# GPRS_Tracker_Sensors.net
KiCad netlist of a schematic drawn in EAGLE
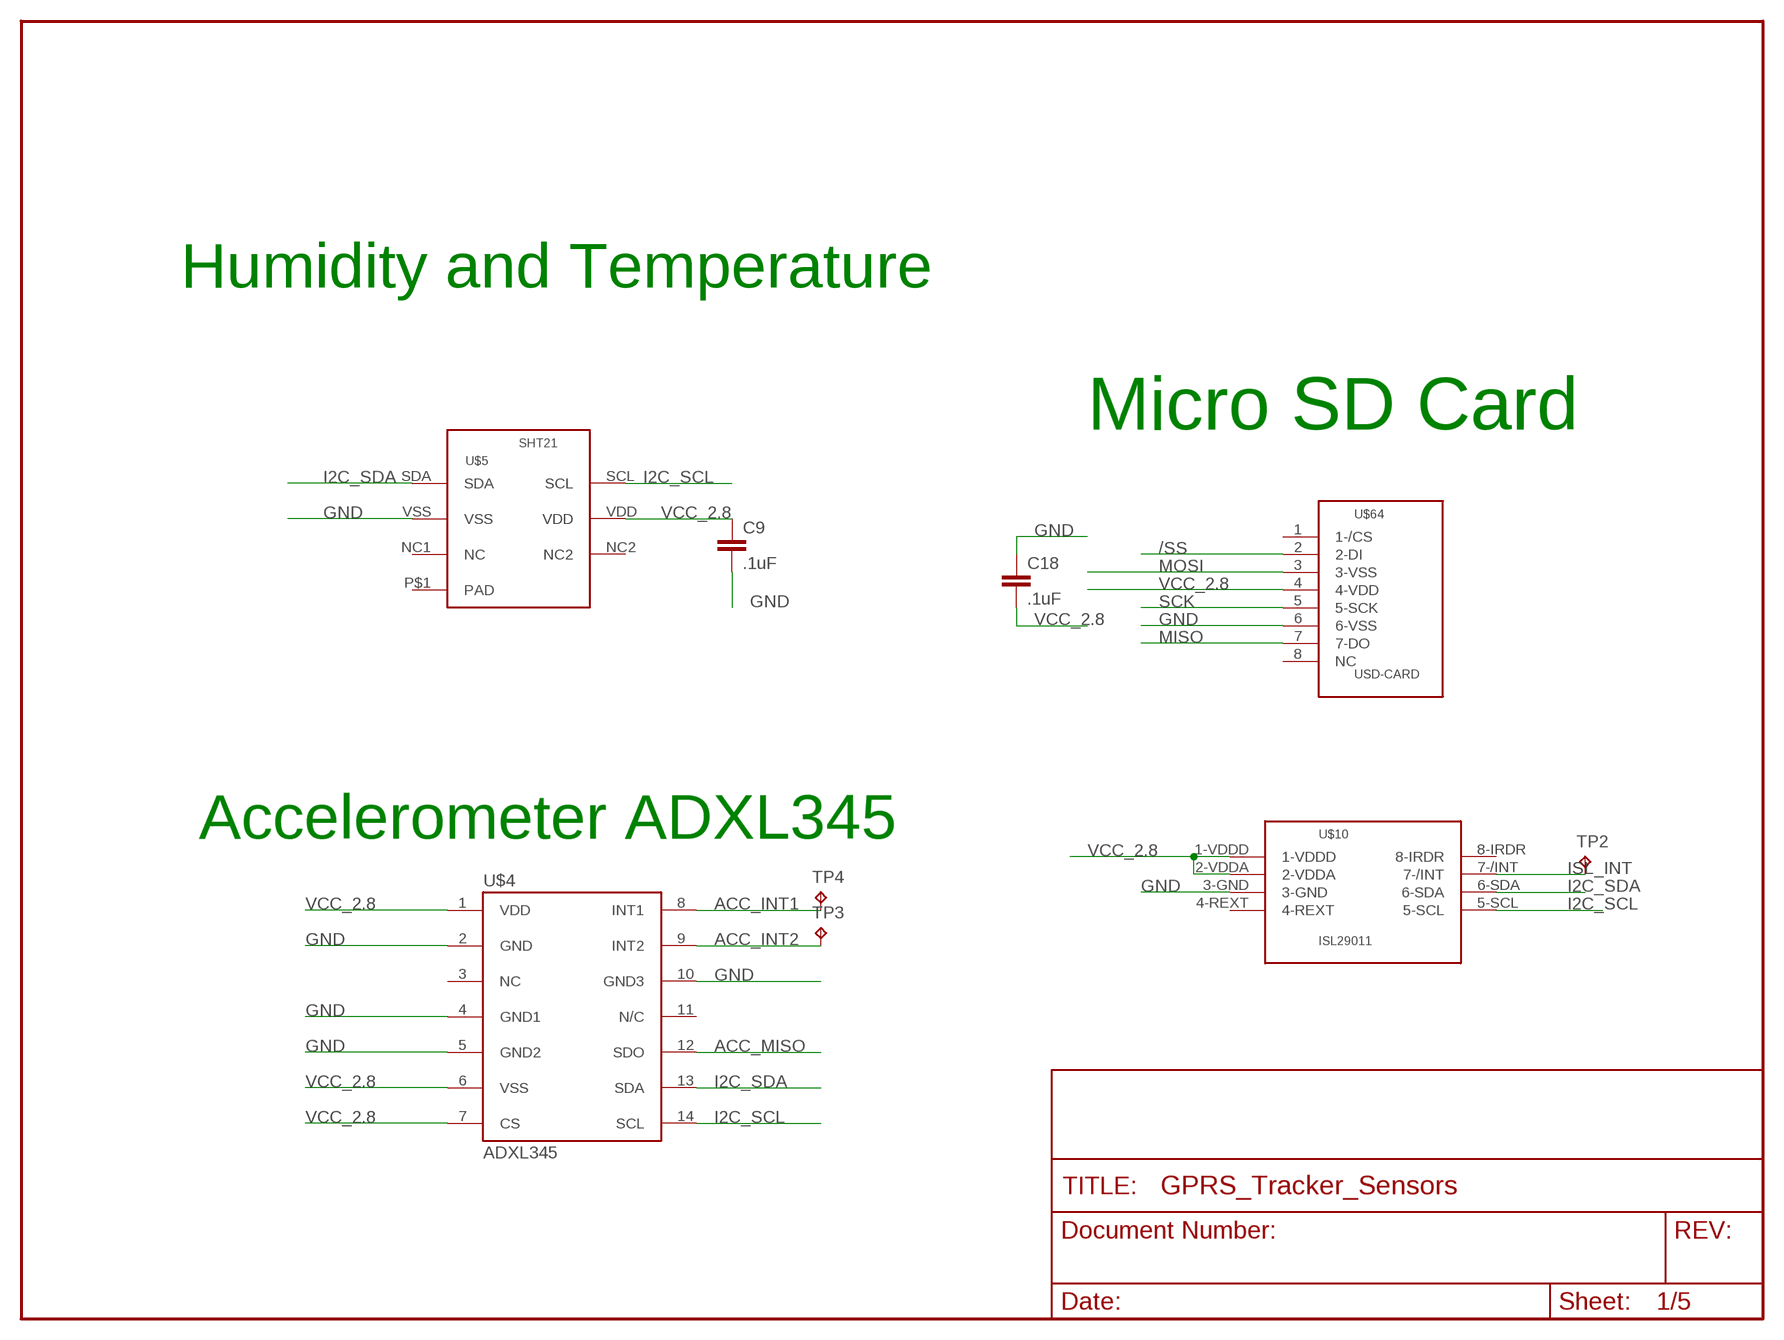
[diagram p0: schematic, sheet 1]
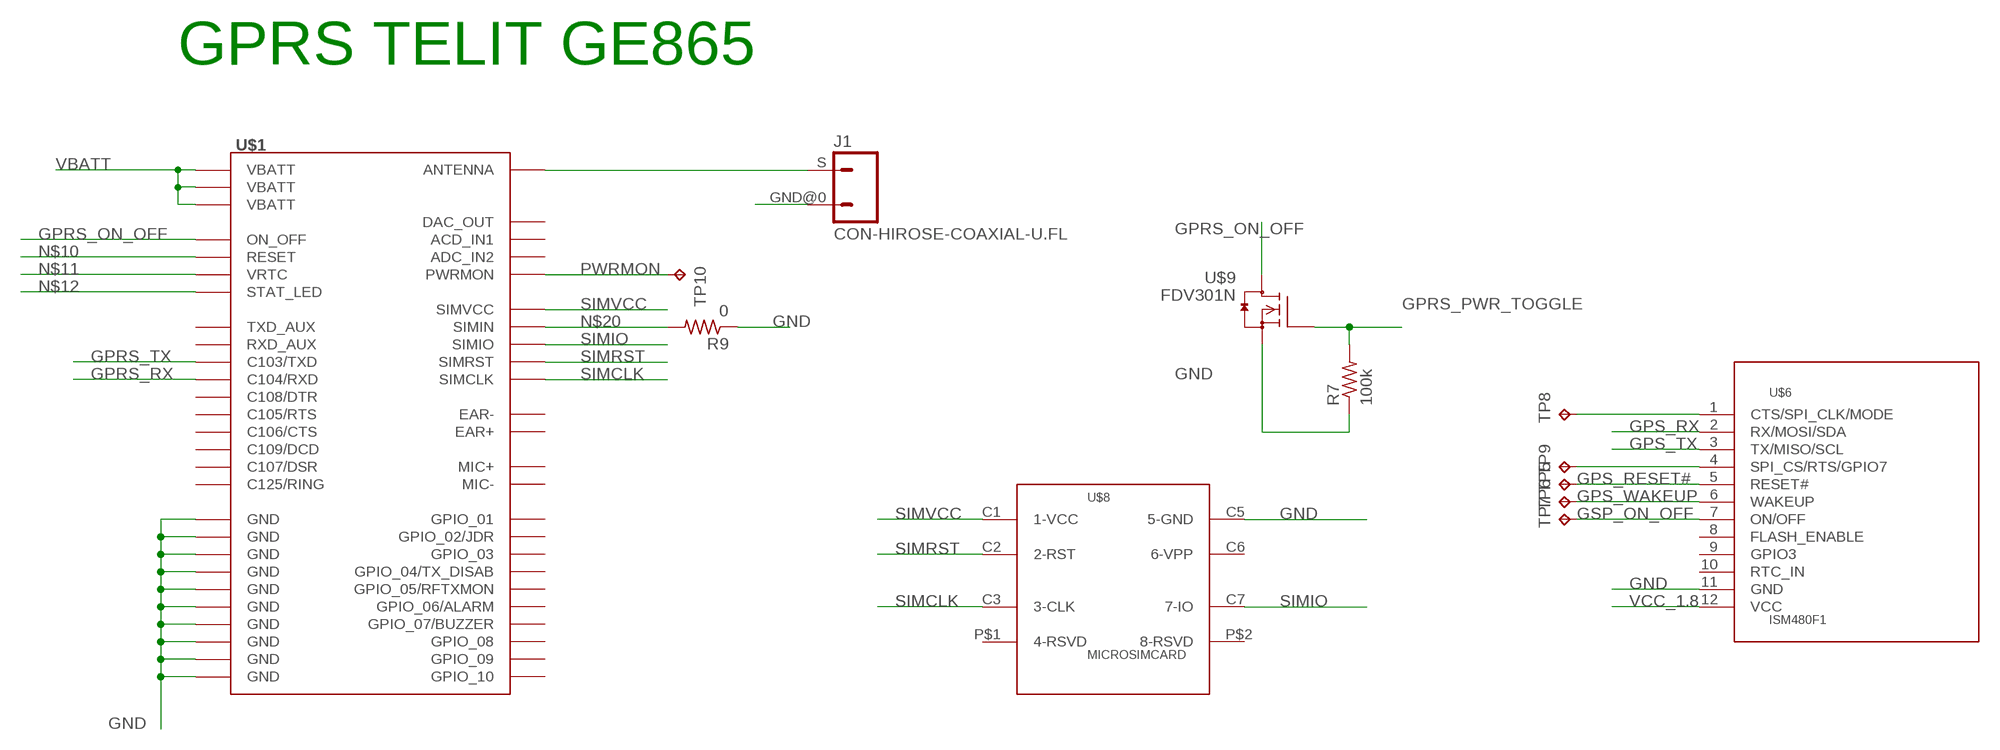
[diagram p1: schematic, sheet 2]
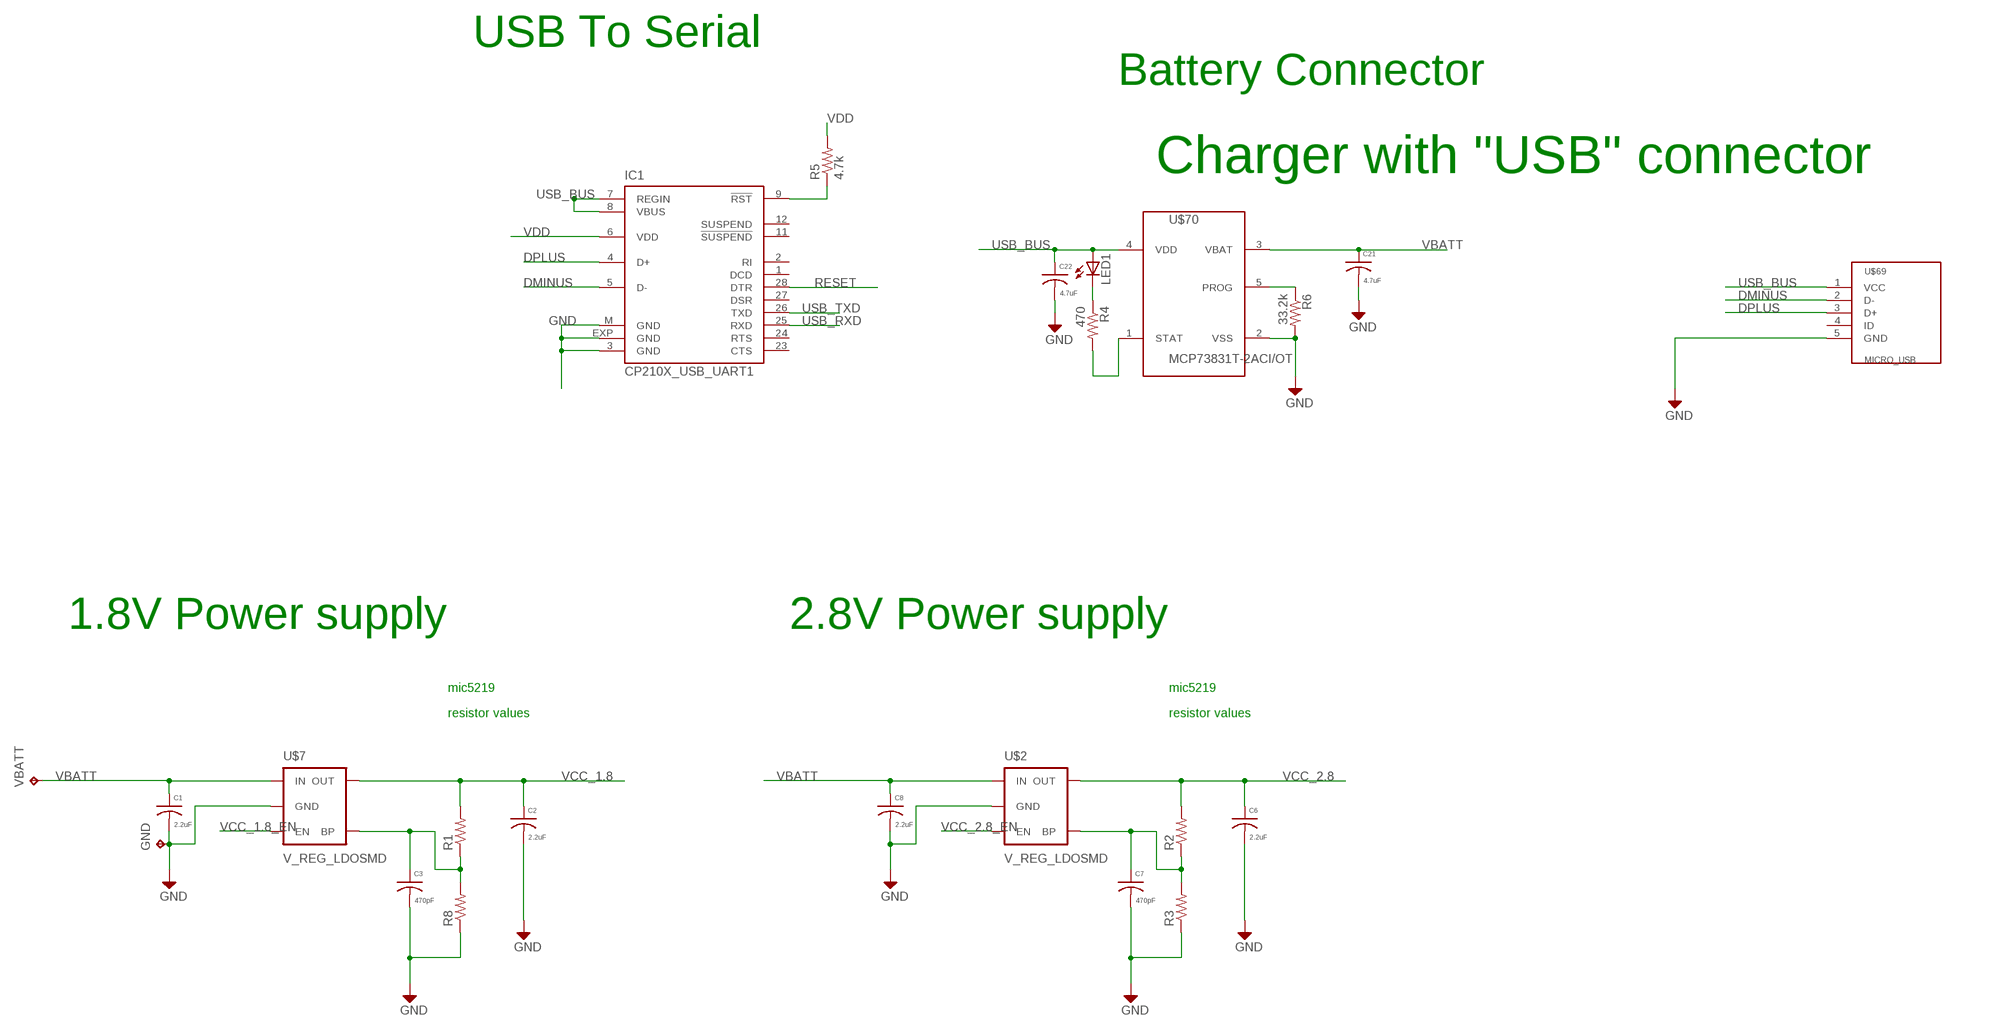
[diagram p2: schematic, sheet 5]

(export (version "E")
  (design (tool "Eeschema 10.0.6"))
  (components
    (comp (ref "C1")
      (value "2.2uF")
      (footprint "eagle-import:C0603")
      (libsource (lib "eagle-import") (part "C0603"))
    )
    (comp (ref "C2")
      (value "2.2uF")
      (footprint "eagle-import:C0603")
      (libsource (lib "eagle-import") (part "C0603"))
    )
    (comp (ref "C3")
      (value "470pF")
      (footprint "eagle-import:C0402")
      (libsource (lib "eagle-import") (part "C0402"))
    )
    (comp (ref "C6")
      (value "2.2uF")
      (footprint "eagle-import:C0603")
      (libsource (lib "eagle-import") (part "C0603"))
    )
    (comp (ref "C7")
      (value "470pF")
      (footprint "eagle-import:C0402")
      (libsource (lib "eagle-import") (part "C0402"))
    )
    (comp (ref "C8")
      (value "2.2uF")
      (footprint "eagle-import:C0603")
      (libsource (lib "eagle-import") (part "C0603"))
    )
    (comp (ref "C21")
      (value "4.7uF")
      (footprint "eagle-import:C0603")
      (libsource (lib "eagle-import") (part "C0603"))
    )
    (comp (ref "C22")
      (value "4.7uF")
      (footprint "eagle-import:C0603")
      (libsource (lib "eagle-import") (part "C0603"))
    )
    (comp (ref "GND")
      (value "TPTP15R")
      (footprint "eagle-import:TP15R")
      (libsource (lib "eagle-import") (part "TPTP15R"))
    )
    (comp (ref "IC1")
      (value "CP210X_USB_UART1")
      (footprint "eagle-import:MLP28")
      (libsource (lib "eagle-import") (part "CP210X_USB_UART1"))
    )
    (comp (ref "LED1")
      (value "LEDCHIP-LED0603")
      (footprint "eagle-import:CHIP-LED0603")
      (libsource (lib "eagle-import") (part "LEDCHIP-LED0603"))
    )
    (comp (ref "R1")
      (value "R-US_R0402")
      (footprint "eagle-import:R0402")
      (libsource (lib "eagle-import") (part "R-US_R0402"))
    )
    (comp (ref "R2")
      (value "R-US_R0402")
      (footprint "eagle-import:R0402")
      (libsource (lib "eagle-import") (part "R-US_R0402"))
    )
    (comp (ref "R3")
      (value "R-US_R0402")
      (footprint "eagle-import:R0402")
      (libsource (lib "eagle-import") (part "R-US_R0402"))
    )
    (comp (ref "R4")
      (value "470")
      (footprint "eagle-import:R0402")
      (libsource (lib "eagle-import") (part "R-US_R0402"))
    )
    (comp (ref "R5")
      (value "4.7k")
      (footprint "eagle-import:R0402")
      (libsource (lib "eagle-import") (part "R-US_R0402"))
    )
    (comp (ref "R6")
      (value "33.2k")
      (footprint "eagle-import:R0402")
      (libsource (lib "eagle-import") (part "R-US_R0402"))
    )
    (comp (ref "R8")
      (value "R-US_R0402")
      (footprint "eagle-import:R0402")
      (libsource (lib "eagle-import") (part "R-US_R0402"))
    )
    (comp (ref "U$2")
      (value "V_REG_LDOSMD")
      (footprint "eagle-import:SOT23-5")
      (libsource (lib "eagle-import") (part "V_REG_LDOSMD"))
    )
    (comp (ref "U$7")
      (value "V_REG_LDOSMD")
      (footprint "eagle-import:SOT23-5")
      (libsource (lib "eagle-import") (part "V_REG_LDOSMD"))
    )
    (comp (ref "U$69")
      (value "MICRO_USB")
      (footprint "eagle-import:MICRO_USB")
      (libsource (lib "eagle-import") (part "MICRO_USB"))
    )
    (comp (ref "U$70")
      (value "MCP73831T-2ACI/OT")
      (footprint "eagle-import:SOT23-5L")
      (libsource (lib "eagle-import") (part "MCP73831T-2ACI/OT"))
    )
    (comp (ref "VBATT")
      (value "TPTP15R")
      (footprint "eagle-import:TP15R")
      (libsource (lib "eagle-import") (part "TPTP15R"))
    )
    (comp (ref "C9")
      (value ".1uF")
      (footprint "eagle-import:C0402")
      (libsource (lib "eagle-import") (part "C-EUC0402"))
    )
    (comp (ref "C18")
      (value ".1uF")
      (footprint "eagle-import:C0402")
      (libsource (lib "eagle-import") (part "C-EUC0402"))
    )
    (comp (ref "TP2")
      (value "TPTP08R")
      (footprint "eagle-import:TP08R")
      (libsource (lib "eagle-import") (part "TPTP08R"))
    )
    (comp (ref "TP3")
      (value "TPTP06R")
      (footprint "eagle-import:TP06R")
      (libsource (lib "eagle-import") (part "TPTP06R"))
    )
    (comp (ref "TP4")
      (value "TPTP06R")
      (footprint "eagle-import:TP06R")
      (libsource (lib "eagle-import") (part "TPTP06R"))
    )
    (comp (ref "U$4")
      (value "ADXL345")
      (footprint "eagle-import:LGA14")
      (libsource (lib "eagle-import") (part "ADXL345"))
    )
    (comp (ref "U$5")
      (value "SHT21")
      (footprint "eagle-import:SHT21")
      (libsource (lib "eagle-import") (part "SHT21"))
    )
    (comp (ref "U$10")
      (value "ISL29011")
      (footprint "eagle-import:ISL29011")
      (libsource (lib "eagle-import") (part "ISL29011"))
    )
    (comp (ref "U$64")
      (value "USD-CARD")
      (footprint "eagle-import:502774-0891")
      (libsource (lib "eagle-import") (part "USD-CARD"))
    )
    (comp (ref "J1")
      (value "CON-HIROSE-COAXIAL-U.FL")
      (footprint "eagle-import:CON-U.FL")
      (libsource (lib "eagle-import") (part "CON-HIROSE-COAXIAL-U.FL"))
    )
    (comp (ref "R7")
      (value "100k")
      (footprint "eagle-import:R0402")
      (libsource (lib "eagle-import") (part "resistor_R-US_R0402"))
    )
    (comp (ref "R9")
      (value "0")
      (footprint "eagle-import:R0402")
      (libsource (lib "eagle-import") (part "resistor_R-US_R0402"))
    )
    (comp (ref "TP5")
      (value "TPTP06R")
      (footprint "eagle-import:TP06R")
      (libsource (lib "eagle-import") (part "TPTP06R"))
    )
    (comp (ref "TP6")
      (value "TPTP06R")
      (footprint "eagle-import:TP06R")
      (libsource (lib "eagle-import") (part "TPTP06R"))
    )
    (comp (ref "TP7")
      (value "TPTP06R")
      (footprint "eagle-import:TP06R")
      (libsource (lib "eagle-import") (part "TPTP06R"))
    )
    (comp (ref "TP8")
      (value "TPTP06R")
      (footprint "eagle-import:TP06R")
      (libsource (lib "eagle-import") (part "TPTP06R"))
    )
    (comp (ref "TP9")
      (value "TPTP06R")
      (footprint "eagle-import:TP06R")
      (libsource (lib "eagle-import") (part "TPTP06R"))
    )
    (comp (ref "TP10")
      (value "TPTP06R")
      (footprint "eagle-import:TP06R")
      (libsource (lib "eagle-import") (part "TPTP06R"))
    )
    (comp (ref "U$1")
      (value "GE865")
      (footprint "eagle-import:GE865")
      (libsource (lib "eagle-import") (part "GE865"))
    )
    (comp (ref "U$6")
      (value "ISM480F1")
      (footprint "eagle-import:20488-012E-01")
      (libsource (lib "eagle-import") (part "ISM480F1"))
    )
    (comp (ref "U$8")
      (value "MICROSIMCARD")
      (footprint "eagle-import:FMS006-5000-0")
      (libsource (lib "eagle-import") (part "MICROSIMCARD"))
    )
    (comp (ref "U$9")
      (value "FDV301N")
      (footprint "eagle-import:SOT23")
      (libsource (lib "eagle-import") (part "FDV301N"))
    )
  )
  (nets
    (net (code "1") (name "ACC_INT1") (class "Default")
      (node (ref "TP4") (pin "TP") (pinfunction "TP_TP") (pintype "input"))
      (node (ref "U$4") (pin "8") (pinfunction "INT1_8") (pintype "bidirectional"))
    )
    (net (code "2") (name "ACC_INT2") (class "Default")
      (node (ref "TP3") (pin "TP") (pinfunction "TP_TP") (pintype "input"))
      (node (ref "U$4") (pin "9") (pinfunction "INT2_9") (pintype "bidirectional"))
    )
    (net (code "3") (name "ACC_MISO") (class "Default")
      (node (ref "U$4") (pin "12") (pinfunction "SDO_12") (pintype "bidirectional"))
    )
    (net (code "4") (name "DMINUS") (class "Default")
      (node (ref "IC1") (pin "5") (pinfunction "D-_5") (pintype "bidirectional"))
      (node (ref "U$69") (pin "2") (pinfunction "D-_2") (pintype "bidirectional"))
    )
    (net (code "5") (name "DPLUS") (class "Default")
      (node (ref "IC1") (pin "4") (pinfunction "D+_4") (pintype "bidirectional"))
      (node (ref "U$69") (pin "3") (pinfunction "D+_3") (pintype "bidirectional"))
    )
    (net (code "6") (name "GND") (class "Default")
      (node (ref "C1") (pin "2") (pinfunction "2_2") (pintype "passive"))
      (node (ref "C18") (pin "1") (pinfunction "1_1") (pintype "passive"))
      (node (ref "C2") (pin "2") (pinfunction "2_2") (pintype "passive"))
      (node (ref "C21") (pin "2") (pinfunction "2_2") (pintype "passive"))
      (node (ref "C22") (pin "2") (pinfunction "2_2") (pintype "passive"))
      (node (ref "C3") (pin "2") (pinfunction "2_2") (pintype "passive"))
      (node (ref "C6") (pin "2") (pinfunction "2_2") (pintype "passive"))
      (node (ref "C7") (pin "2") (pinfunction "2_2") (pintype "passive"))
      (node (ref "C8") (pin "2") (pinfunction "2_2") (pintype "passive"))
      (node (ref "C9") (pin "2") (pinfunction "2_2") (pintype "passive"))
      (node (ref "GND") (pin "TP") (pinfunction "TP_TP") (pintype "input"))
      (node (ref "IC1") (pin "3") (pinfunction "GND_3") (pintype "power_in"))
      (node (ref "IC1") (pin "EXP") (pinfunction "GND_EXP") (pintype "power_in"))
      (node (ref "IC1") (pin "M") (pinfunction "GND_M") (pintype "power_in"))
      (node (ref "R3") (pin "1") (pinfunction "1_1") (pintype "passive"))
      (node (ref "R6") (pin "2") (pinfunction "2_2") (pintype "passive"))
      (node (ref "R7") (pin "1") (pinfunction "1_1") (pintype "passive"))
      (node (ref "R8") (pin "1") (pinfunction "1_1") (pintype "passive"))
      (node (ref "R9") (pin "1") (pinfunction "1_1") (pintype "passive"))
      (node (ref "U$1") (pin "C2") (pinfunction "GND_C2") (pintype "bidirectional"))
      (node (ref "U$1") (pin "C7") (pinfunction "GND_C7") (pintype "bidirectional"))
      (node (ref "U$1") (pin "E5") (pinfunction "GND_E5") (pintype "bidirectional"))
      (node (ref "U$1") (pin "E7") (pinfunction "GND_E7") (pintype "bidirectional"))
      (node (ref "U$1") (pin "G1") (pinfunction "GND_G1") (pintype "bidirectional"))
      (node (ref "U$1") (pin "G3") (pinfunction "GND_G3") (pintype "bidirectional"))
      (node (ref "U$1") (pin "G4") (pinfunction "GND_G4") (pintype "bidirectional"))
      (node (ref "U$1") (pin "G5") (pinfunction "GND_G5") (pintype "bidirectional"))
      (node (ref "U$1") (pin "H3") (pinfunction "GND_H3") (pintype "bidirectional"))
      (node (ref "U$1") (pin "H6") (pinfunction "GND_H6") (pintype "bidirectional"))
      (node (ref "U$10") (pin "3-GND") (pinfunction "3-GND_3-GND") (pintype "bidirectional"))
      (node (ref "U$2") (pin "2") (pinfunction "GND_2") (pintype "input"))
      (node (ref "U$4") (pin "10") (pinfunction "GND3_10") (pintype "bidirectional"))
      (node (ref "U$4") (pin "2") (pinfunction "GND_2") (pintype "bidirectional"))
      (node (ref "U$4") (pin "4") (pinfunction "GND1_4") (pintype "bidirectional"))
      (node (ref "U$4") (pin "5") (pinfunction "GND2_5") (pintype "bidirectional"))
      (node (ref "U$5") (pin "VSS") (pinfunction "VSS_VSS") (pintype "bidirectional"))
      (node (ref "U$6") (pin "11") (pinfunction "GND_11") (pintype "bidirectional"))
      (node (ref "U$64") (pin "6") (pinfunction "6-VSS_6") (pintype "bidirectional"))
      (node (ref "U$69") (pin "5") (pinfunction "GND_5") (pintype "bidirectional"))
      (node (ref "U$7") (pin "2") (pinfunction "GND_2") (pintype "input"))
      (node (ref "U$70") (pin "2") (pinfunction "VSS_2") (pintype "bidirectional"))
      (node (ref "U$8") (pin "C5") (pinfunction "5-GND_C5") (pintype "bidirectional"))
      (node (ref "U$9") (pin "2") (pinfunction "S_2") (pintype "passive"))
    )
    (net (code "7") (name "GPRS_ON_OFF") (class "Default")
      (node (ref "U$1") (pin "B1") (pinfunction "ON_OFF_B1") (pintype "bidirectional"))
      (node (ref "U$9") (pin "3") (pinfunction "D_3") (pintype "passive"))
    )
    (net (code "8") (name "GPRS_PWR_TOGGLE") (class "Default")
      (node (ref "R7") (pin "2") (pinfunction "2_2") (pintype "passive"))
      (node (ref "U$9") (pin "1") (pinfunction "G_1") (pintype "passive"))
    )
    (net (code "9") (name "GPRS_RX") (class "Default")
      (node (ref "U$1") (pin "A4") (pinfunction "C104/RXD_A4") (pintype "bidirectional"))
    )
    (net (code "10") (name "GPRS_TX") (class "Default")
      (node (ref "U$1") (pin "A3") (pinfunction "C103/TXD_A3") (pintype "bidirectional"))
    )
    (net (code "11") (name "GPS_RESET#") (class "Default")
      (node (ref "TP5") (pin "TP") (pinfunction "TP_TP") (pintype "input"))
      (node (ref "U$6") (pin "5") (pinfunction "RESET#_5") (pintype "bidirectional"))
    )
    (net (code "12") (name "GPS_RX") (class "Default")
      (node (ref "U$6") (pin "2") (pinfunction "RX/MOSI/SDA_2") (pintype "bidirectional"))
    )
    (net (code "13") (name "GPS_TX") (class "Default")
      (node (ref "U$6") (pin "3") (pinfunction "TX/MISO/SCL_3") (pintype "bidirectional"))
    )
    (net (code "14") (name "GPS_WAKEUP") (class "Default")
      (node (ref "TP6") (pin "TP") (pinfunction "TP_TP") (pintype "input"))
      (node (ref "U$6") (pin "6") (pinfunction "WAKEUP_6") (pintype "bidirectional"))
    )
    (net (code "15") (name "GSP_ON_OFF") (class "Default")
      (node (ref "TP7") (pin "TP") (pinfunction "TP_TP") (pintype "input"))
      (node (ref "U$6") (pin "7") (pinfunction "ON/OFF_7") (pintype "bidirectional"))
    )
    (net (code "16") (name "I2C_SCL") (class "Default")
      (node (ref "U$10") (pin "5-SCL") (pinfunction "5-SCL_5-SCL") (pintype "bidirectional"))
      (node (ref "U$4") (pin "14") (pinfunction "SCL_14") (pintype "bidirectional"))
      (node (ref "U$5") (pin "SCL") (pinfunction "SCL_SCL") (pintype "bidirectional"))
    )
    (net (code "17") (name "I2C_SDA") (class "Default")
      (node (ref "U$10") (pin "6-SDA") (pinfunction "6-SDA_6-SDA") (pintype "bidirectional"))
      (node (ref "U$4") (pin "13") (pinfunction "SDA_13") (pintype "bidirectional"))
      (node (ref "U$5") (pin "SDA") (pinfunction "SDA_SDA") (pintype "bidirectional"))
    )
    (net (code "18") (name "ISL_INT") (class "Default")
      (node (ref "TP2") (pin "TP") (pinfunction "TP_TP") (pintype "input"))
      (node (ref "U$10") (pin "7-/INT") (pinfunction "7-/INT_7-/INT") (pintype "bidirectional"))
    )
    (net (code "19") (name "MISO") (class "Default")
      (node (ref "U$64") (pin "7") (pinfunction "7-DO_7") (pintype "bidirectional"))
    )
    (net (code "20") (name "MOSI") (class "Default")
      (node (ref "U$64") (pin "3") (pinfunction "3-VSS_3") (pintype "bidirectional"))
    )
    (net (code "21") (name "N$10") (class "Default")
      (node (ref "U$1") (pin "C1") (pinfunction "RESET_C1") (pintype "bidirectional"))
    )
    (net (code "22") (name "N$11") (class "Default")
      (node (ref "U$1") (pin "H2") (pinfunction "VRTC_H2") (pintype "bidirectional"))
    )
    (net (code "23") (name "N$12") (class "Default")
      (node (ref "U$1") (pin "G8") (pinfunction "STAT_LED_G8") (pintype "bidirectional"))
    )
    (net (code "24") (name "N$20") (class "Default")
      (node (ref "R9") (pin "2") (pinfunction "2_2") (pintype "passive"))
      (node (ref "U$1") (pin "B7") (pinfunction "SIMIN_B7") (pintype "bidirectional"))
    )
    (net (code "25") (name "Net-(IC1-~{RST})") (class "Default")
      (node (ref "IC1") (pin "9") (pinfunction "~{RST}_9") (pintype "bidirectional"))
      (node (ref "R5") (pin "1") (pinfunction "1_1") (pintype "passive"))
    )
    (net (code "26") (name "Net-(J1-1)") (class "Default")
      (node (ref "J1") (pin "S") (pinfunction "1_S") (pintype "passive"))
      (node (ref "U$1") (pin "H5") (pinfunction "ANTENNA_H5") (pintype "bidirectional"))
    )
    (net (code "27") (name "Net-(LED1-PadC)") (class "Default")
      (node (ref "LED1") (pin "C") (pinfunction "C_C") (pintype "passive"))
      (node (ref "R4") (pin "1") (pinfunction "1_1") (pintype "passive"))
    )
    (net (code "28") (name "Net-(U$2-BP)") (class "Default")
      (node (ref "C7") (pin "1") (pinfunction "1_1") (pintype "passive"))
      (node (ref "R2") (pin "1") (pinfunction "1_1") (pintype "passive"))
      (node (ref "R3") (pin "2") (pinfunction "2_2") (pintype "passive"))
      (node (ref "U$2") (pin "4") (pinfunction "BP_4") (pintype "input"))
    )
    (net (code "29") (name "Net-(U$6-CTS{slash}SPI_CLK{slash}MODE)") (class "Default")
      (node (ref "TP8") (pin "TP") (pinfunction "TP_TP") (pintype "input"))
      (node (ref "U$6") (pin "1") (pinfunction "CTS/SPI_CLK/MODE_1") (pintype "bidirectional"))
    )
    (net (code "30") (name "Net-(U$6-SPI_CS{slash}RTS{slash}GPIO7)") (class "Default")
      (node (ref "TP9") (pin "TP") (pinfunction "TP_TP") (pintype "input"))
      (node (ref "U$6") (pin "4") (pinfunction "SPI_CS/RTS/GPIO7_4") (pintype "bidirectional"))
    )
    (net (code "31") (name "Net-(U$7-BP)") (class "Default")
      (node (ref "C3") (pin "1") (pinfunction "1_1") (pintype "passive"))
      (node (ref "R1") (pin "1") (pinfunction "1_1") (pintype "passive"))
      (node (ref "R8") (pin "2") (pinfunction "2_2") (pintype "passive"))
      (node (ref "U$7") (pin "4") (pinfunction "BP_4") (pintype "input"))
    )
    (net (code "32") (name "Net-(U$70-PROG)") (class "Default")
      (node (ref "R6") (pin "1") (pinfunction "1_1") (pintype "passive"))
      (node (ref "U$70") (pin "5") (pinfunction "PROG_5") (pintype "bidirectional"))
    )
    (net (code "33") (name "Net-(U$70-STAT)") (class "Default")
      (node (ref "R4") (pin "2") (pinfunction "2_2") (pintype "passive"))
      (node (ref "U$70") (pin "1") (pinfunction "STAT_1") (pintype "bidirectional"))
    )
    (net (code "34") (name "PWRMON") (class "Default")
      (node (ref "TP10") (pin "TP") (pinfunction "TP_TP") (pintype "input"))
      (node (ref "U$1") (pin "E2") (pinfunction "PWRMON_E2") (pintype "bidirectional"))
    )
    (net (code "35") (name "RESET") (class "Default")
      (node (ref "IC1") (pin "28") (pinfunction "DTR_28") (pintype "output"))
    )
    (net (code "36") (name "SCK") (class "Default")
      (node (ref "U$64") (pin "5") (pinfunction "5-SCK_5") (pintype "bidirectional"))
    )
    (net (code "37") (name "SIMCLK") (class "Default")
      (node (ref "U$1") (pin "A5") (pinfunction "SIMCLK_A5") (pintype "bidirectional"))
      (node (ref "U$8") (pin "C3") (pinfunction "3-CLK_C3") (pintype "bidirectional"))
    )
    (net (code "38") (name "SIMIO") (class "Default")
      (node (ref "U$1") (pin "A6") (pinfunction "SIMIO_A6") (pintype "bidirectional"))
      (node (ref "U$8") (pin "C7") (pinfunction "7-IO_C7") (pintype "bidirectional"))
    )
    (net (code "39") (name "SIMRST") (class "Default")
      (node (ref "U$1") (pin "A8") (pinfunction "SIMRST_A8") (pintype "bidirectional"))
      (node (ref "U$8") (pin "C2") (pinfunction "2-RST_C2") (pintype "bidirectional"))
    )
    (net (code "40") (name "SIMVCC") (class "Default")
      (node (ref "U$1") (pin "A7") (pinfunction "SIMVCC_A7") (pintype "bidirectional"))
      (node (ref "U$8") (pin "C1") (pinfunction "1-VCC_C1") (pintype "bidirectional"))
    )
    (net (code "41") (name "USB_BUS") (class "Default")
      (node (ref "C22") (pin "1") (pinfunction "1_1") (pintype "passive"))
      (node (ref "IC1") (pin "7") (pinfunction "REGIN_7") (pintype "passive"))
      (node (ref "IC1") (pin "8") (pinfunction "VBUS_8") (pintype "input"))
      (node (ref "LED1") (pin "A") (pinfunction "A_A") (pintype "passive"))
      (node (ref "U$69") (pin "1") (pinfunction "VCC_1") (pintype "bidirectional"))
      (node (ref "U$70") (pin "4") (pinfunction "VDD_4") (pintype "bidirectional"))
    )
    (net (code "42") (name "USB_RXD") (class "Default")
      (node (ref "IC1") (pin "25") (pinfunction "RXD_25") (pintype "input"))
    )
    (net (code "43") (name "USB_TXD") (class "Default")
      (node (ref "IC1") (pin "26") (pinfunction "TXD_26") (pintype "output"))
    )
    (net (code "44") (name "VBATT") (class "Default")
      (node (ref "C1") (pin "1") (pinfunction "1_1") (pintype "passive"))
      (node (ref "C21") (pin "1") (pinfunction "1_1") (pintype "passive"))
      (node (ref "C8") (pin "1") (pinfunction "1_1") (pintype "passive"))
      (node (ref "U$1") (pin "F1") (pinfunction "VBATT_F1") (pintype "bidirectional"))
      (node (ref "U$1") (pin "F2") (pinfunction "VBATT_F2") (pintype "bidirectional"))
      (node (ref "U$1") (pin "F3") (pinfunction "VBATT_F3") (pintype "bidirectional"))
      (node (ref "U$2") (pin "1") (pinfunction "IN_1") (pintype "input"))
      (node (ref "U$7") (pin "1") (pinfunction "IN_1") (pintype "input"))
      (node (ref "U$70") (pin "3") (pinfunction "VBAT_3") (pintype "bidirectional"))
      (node (ref "VBATT") (pin "TP") (pinfunction "TP_TP") (pintype "input"))
    )
    (net (code "45") (name "VCC_1.8") (class "Default")
      (node (ref "C2") (pin "1") (pinfunction "1_1") (pintype "passive"))
      (node (ref "R1") (pin "2") (pinfunction "2_2") (pintype "passive"))
      (node (ref "U$6") (pin "12") (pinfunction "VCC_12") (pintype "bidirectional"))
      (node (ref "U$7") (pin "5") (pinfunction "OUT_5") (pintype "passive"))
    )
    (net (code "46") (name "VCC_1.8_EN") (class "Default")
      (node (ref "U$7") (pin "3") (pinfunction "EN_3") (pintype "input"))
    )
    (net (code "47") (name "VCC_2.8") (class "Default")
      (node (ref "C18") (pin "2") (pinfunction "2_2") (pintype "passive"))
      (node (ref "C6") (pin "1") (pinfunction "1_1") (pintype "passive"))
      (node (ref "C9") (pin "1") (pinfunction "1_1") (pintype "passive"))
      (node (ref "R2") (pin "2") (pinfunction "2_2") (pintype "passive"))
      (node (ref "U$10") (pin "1-VDDD") (pinfunction "1-VDDD_1-VDDD") (pintype "bidirectional"))
      (node (ref "U$10") (pin "2-VDDA") (pinfunction "2-VDDA_2-VDDA") (pintype "bidirectional"))
      (node (ref "U$2") (pin "5") (pinfunction "OUT_5") (pintype "passive"))
      (node (ref "U$4") (pin "1") (pinfunction "VDD_1") (pintype "bidirectional"))
      (node (ref "U$4") (pin "6") (pinfunction "VSS_6") (pintype "bidirectional"))
      (node (ref "U$4") (pin "7") (pinfunction "CS_7") (pintype "bidirectional"))
      (node (ref "U$5") (pin "VDD") (pinfunction "VDD_VDD") (pintype "bidirectional"))
      (node (ref "U$64") (pin "4") (pinfunction "4-VDD_4") (pintype "bidirectional"))
    )
    (net (code "48") (name "VCC_2.8_EN") (class "Default")
      (node (ref "U$2") (pin "3") (pinfunction "EN_3") (pintype "input"))
    )
    (net (code "49") (name "VDD") (class "Default")
      (node (ref "IC1") (pin "6") (pinfunction "VDD_6") (pintype "power_in"))
      (node (ref "R5") (pin "2") (pinfunction "2_2") (pintype "passive"))
    )
    (net (code "50") (name "unconnected-(IC1-CTS-Pad23)") (class "Default")
      (node (ref "IC1") (pin "23") (pinfunction "CTS_23") (pintype "input"))
    )
    (net (code "51") (name "unconnected-(IC1-DCD-Pad1)") (class "Default")
      (node (ref "IC1") (pin "1") (pinfunction "DCD_1") (pintype "input"))
    )
    (net (code "52") (name "unconnected-(IC1-DSR-Pad27)") (class "Default")
      (node (ref "IC1") (pin "27") (pinfunction "DSR_27") (pintype "input"))
    )
    (net (code "53") (name "unconnected-(IC1-RI-Pad2)") (class "Default")
      (node (ref "IC1") (pin "2") (pinfunction "RI_2") (pintype "input"))
    )
    (net (code "54") (name "unconnected-(IC1-RTS-Pad24)") (class "Default")
      (node (ref "IC1") (pin "24") (pinfunction "RTS_24") (pintype "output"))
    )
    (net (code "55") (name "unconnected-(IC1-SUSPEND-Pad12)") (class "Default")
      (node (ref "IC1") (pin "12") (pinfunction "SUSPEND_12") (pintype "output"))
    )
    (net (code "56") (name "unconnected-(IC1-~{SUSPEND}-Pad11)") (class "Default")
      (node (ref "IC1") (pin "11") (pinfunction "~{SUSPEND}_11") (pintype "output"))
    )
    (net (code "57") (name "unconnected-(J1-2-PadGND@0)") (class "Default")
      (node (ref "J1") (pin "GND@0") (pinfunction "2_GND@0") (pintype "passive"))
    )
    (net (code "58") (name "unconnected-(U$1-ACD_IN1-PadF5)") (class "Default")
      (node (ref "U$1") (pin "F5") (pinfunction "ACD_IN1_F5") (pintype "bidirectional"))
    )
    (net (code "59") (name "unconnected-(U$1-ADC_IN2-PadF6)") (class "Default")
      (node (ref "U$1") (pin "F6") (pinfunction "ADC_IN2_F6") (pintype "bidirectional"))
    )
    (net (code "60") (name "unconnected-(U$1-C105{slash}RTS-PadA1)") (class "Default")
      (node (ref "U$1") (pin "A1") (pinfunction "C105/RTS_A1") (pintype "bidirectional"))
    )
    (net (code "61") (name "unconnected-(U$1-C106{slash}CTS-PadA2)") (class "Default")
      (node (ref "U$1") (pin "A2") (pinfunction "C106/CTS_A2") (pintype "bidirectional"))
    )
    (net (code "62") (name "unconnected-(U$1-C107{slash}DSR-PadB2)") (class "Default")
      (node (ref "U$1") (pin "B2") (pinfunction "C107/DSR_B2") (pintype "bidirectional"))
    )
    (net (code "63") (name "unconnected-(U$1-C108{slash}DTR-PadB3)") (class "Default")
      (node (ref "U$1") (pin "B3") (pinfunction "C108/DTR_B3") (pintype "bidirectional"))
    )
    (net (code "64") (name "unconnected-(U$1-C109{slash}DCD-PadB5)") (class "Default")
      (node (ref "U$1") (pin "B5") (pinfunction "C109/DCD_B5") (pintype "bidirectional"))
    )
    (net (code "65") (name "unconnected-(U$1-C125{slash}RING-PadB4)") (class "Default")
      (node (ref "U$1") (pin "B4") (pinfunction "C125/RING_B4") (pintype "bidirectional"))
    )
    (net (code "66") (name "unconnected-(U$1-DAC_OUT-PadG7)") (class "Default")
      (node (ref "U$1") (pin "G7") (pinfunction "DAC_OUT_G7") (pintype "bidirectional"))
    )
    (net (code "67") (name "unconnected-(U$1-EAR+-PadD8)") (class "Default")
      (node (ref "U$1") (pin "D8") (pinfunction "EAR+_D8") (pintype "bidirectional"))
    )
    (net (code "68") (name "unconnected-(U$1-EAR--PadE8)") (class "Default")
      (node (ref "U$1") (pin "E8") (pinfunction "EAR-_E8") (pintype "bidirectional"))
    )
    (net (code "69") (name "unconnected-(U$1-GPIO_01-PadD3)") (class "Default")
      (node (ref "U$1") (pin "D3") (pinfunction "GPIO_01_D3") (pintype "bidirectional"))
    )
    (net (code "70") (name "unconnected-(U$1-GPIO_02{slash}JDR-PadD2)") (class "Default")
      (node (ref "U$1") (pin "D2") (pinfunction "GPIO_02/JDR_D2") (pintype "bidirectional"))
    )
    (net (code "71") (name "unconnected-(U$1-GPIO_03-PadE4)") (class "Default")
      (node (ref "U$1") (pin "E4") (pinfunction "GPIO_03_E4") (pintype "bidirectional"))
    )
    (net (code "72") (name "unconnected-(U$1-GPIO_04{slash}TX_DISAB-PadH7)") (class "Default")
      (node (ref "U$1") (pin "H7") (pinfunction "GPIO_04/TX_DISAB_H7") (pintype "bidirectional"))
    )
    (net (code "73") (name "unconnected-(U$1-GPIO_05{slash}RFTXMON-PadG2)") (class "Default")
      (node (ref "U$1") (pin "G2") (pinfunction "GPIO_05/RFTXMON_G2") (pintype "bidirectional"))
    )
    (net (code "74") (name "unconnected-(U$1-GPIO_06{slash}ALARM-PadH8)") (class "Default")
      (node (ref "U$1") (pin "H8") (pinfunction "GPIO_06/ALARM_H8") (pintype "bidirectional"))
    )
    (net (code "75") (name "unconnected-(U$1-GPIO_07{slash}BUZZER-PadG6)") (class "Default")
      (node (ref "U$1") (pin "G6") (pinfunction "GPIO_07/BUZZER_G6") (pintype "bidirectional"))
    )
    (net (code "76") (name "unconnected-(U$1-GPIO_08-PadD4)") (class "Default")
      (node (ref "U$1") (pin "D4") (pinfunction "GPIO_08_D4") (pintype "bidirectional"))
    )
    (net (code "77") (name "unconnected-(U$1-GPIO_09-PadF4)") (class "Default")
      (node (ref "U$1") (pin "F4") (pinfunction "GPIO_09_F4") (pintype "bidirectional"))
    )
    (net (code "78") (name "unconnected-(U$1-GPIO_10-PadE3)") (class "Default")
      (node (ref "U$1") (pin "E3") (pinfunction "GPIO_10_E3") (pintype "bidirectional"))
    )
    (net (code "79") (name "unconnected-(U$1-MIC+-PadB8)") (class "Default")
      (node (ref "U$1") (pin "B8") (pinfunction "MIC+_B8") (pintype "bidirectional"))
    )
    (net (code "80") (name "unconnected-(U$1-MIC--PadC8)") (class "Default")
      (node (ref "U$1") (pin "C8") (pinfunction "MIC-_C8") (pintype "bidirectional"))
    )
    (net (code "81") (name "unconnected-(U$1-RXD_AUX-PadE1)") (class "Default")
      (node (ref "U$1") (pin "E1") (pinfunction "RXD_AUX_E1") (pintype "bidirectional"))
    )
    (net (code "82") (name "unconnected-(U$1-TXD_AUX-PadD1)") (class "Default")
      (node (ref "U$1") (pin "D1") (pinfunction "TXD_AUX_D1") (pintype "bidirectional"))
    )
    (net (code "83") (name "unconnected-(U$4-NC-Pad3)") (class "Default")
      (node (ref "U$4") (pin "3") (pinfunction "NC_3") (pintype "bidirectional"))
    )
    (net (code "84") (name "unconnected-(U$4-N{slash}C-Pad11)") (class "Default")
      (node (ref "U$4") (pin "11") (pinfunction "N/C_11") (pintype "bidirectional"))
    )
    (net (code "85") (name "unconnected-(U$5-NC-PadNC1)") (class "Default")
      (node (ref "U$5") (pin "NC1") (pinfunction "NC_NC1") (pintype "bidirectional"))
    )
    (net (code "86") (name "unconnected-(U$5-PAD-PadP$1)") (class "Default")
      (node (ref "U$5") (pin "P$1") (pinfunction "PAD_P$1") (pintype "bidirectional"))
    )
    (net (code "87") (name "unconnected-(U$5-PadNC2)") (class "Default")
      (node (ref "U$5") (pin "NC2") (pinfunction "NC2_NC2") (pintype "bidirectional"))
    )
    (net (code "88") (name "unconnected-(U$6-FLASH_ENABLE-Pad8)") (class "Default")
      (node (ref "U$6") (pin "8") (pinfunction "FLASH_ENABLE_8") (pintype "bidirectional"))
    )
    (net (code "89") (name "unconnected-(U$6-GPIO3-Pad9)") (class "Default")
      (node (ref "U$6") (pin "9") (pinfunction "GPIO3_9") (pintype "bidirectional"))
    )
    (net (code "90") (name "unconnected-(U$6-RTC_IN-Pad10)") (class "Default")
      (node (ref "U$6") (pin "10") (pinfunction "RTC_IN_10") (pintype "bidirectional"))
    )
    (net (code "91") (name "unconnected-(U$8-4-RSVD-PadP$1)") (class "Default")
      (node (ref "U$8") (pin "P$1") (pinfunction "4-RSVD_P$1") (pintype "bidirectional"))
    )
    (net (code "92") (name "unconnected-(U$8-6-VPP-PadC6)") (class "Default")
      (node (ref "U$8") (pin "C6") (pinfunction "6-VPP_C6") (pintype "bidirectional"))
    )
    (net (code "93") (name "unconnected-(U$8-8-RSVD-PadP$2)") (class "Default")
      (node (ref "U$8") (pin "P$2") (pinfunction "8-RSVD_P$2") (pintype "bidirectional"))
    )
    (net (code "94") (name "unconnected-(U$10-Pad4-REXT)") (class "Default")
      (node (ref "U$10") (pin "4-REXT") (pinfunction "4-REXT_4-REXT") (pintype "bidirectional"))
    )
    (net (code "95") (name "unconnected-(U$10-Pad8-IRDR)") (class "Default")
      (node (ref "U$10") (pin "8-IRDR") (pinfunction "8-IRDR_8-IRDR") (pintype "bidirectional"))
    )
    (net (code "96") (name "unconnected-(U$64-1-{slash}CS-Pad1)") (class "Default")
      (node (ref "U$64") (pin "1") (pinfunction "1-/CS_1") (pintype "bidirectional"))
    )
    (net (code "97") (name "unconnected-(U$64-NC-Pad8)") (class "Default")
      (node (ref "U$64") (pin "8") (pinfunction "NC_8") (pintype "bidirectional"))
    )
    (net (code "98") (name "unconnected-(U$69-ID-Pad4)") (class "Default")
      (node (ref "U$69") (pin "4") (pinfunction "ID_4") (pintype "bidirectional"))
    )
    (net (code "99") (name "{slash}SS") (class "Default")
      (node (ref "U$64") (pin "2") (pinfunction "2-DI_2") (pintype "bidirectional"))
    )
  )
)
